# AtariPunkConsole.net
KiCad netlist of a schematic drawn in EAGLE
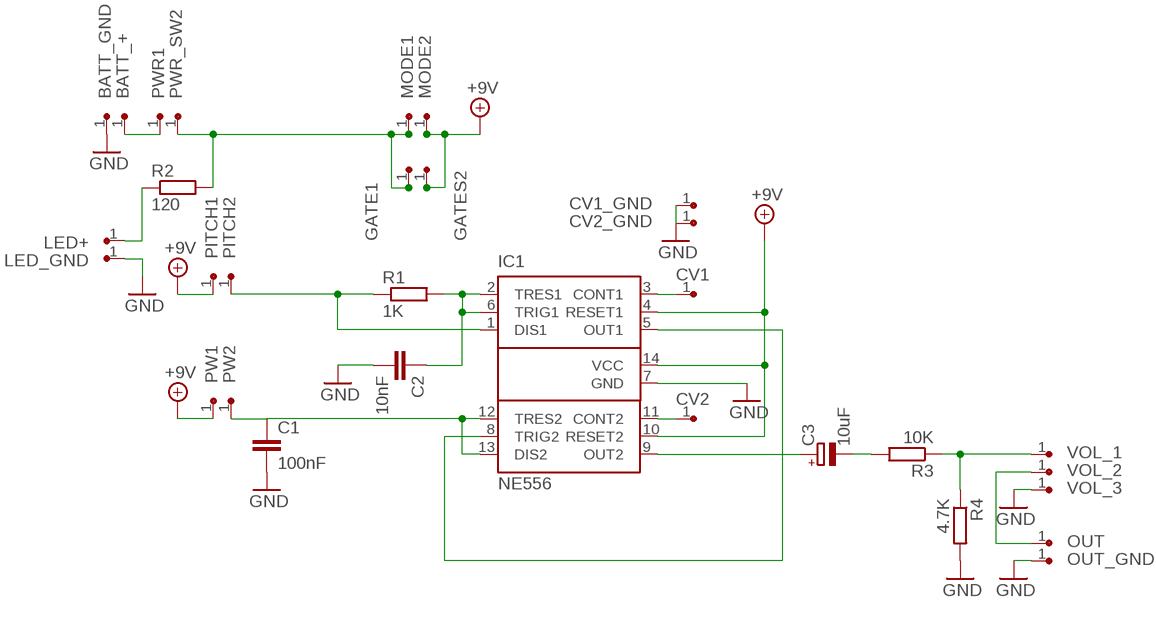
[diagram p0: schematic, sheet 1]

(export (version "E")
  (design (tool "Eeschema 10.0.6"))
  (components
    (comp (ref "BATT_+")
      (value "CV1")
      (footprint "eagle-import:SINGLE_PAD")
      (libsource (lib "eagle-import") (part "SINGLE_PAD"))
    )
    (comp (ref "BATT_GND")
      (value "CV1")
      (footprint "eagle-import:SINGLE_PAD")
      (libsource (lib "eagle-import") (part "SINGLE_PAD"))
    )
    (comp (ref "C1")
      (value "100nF")
      (footprint "eagle-import:C050-025X075")
      (libsource (lib "eagle-import") (part "C-EU050-025X075"))
    )
    (comp (ref "C2")
      (value "10nF")
      (footprint "eagle-import:C050-025X075")
      (libsource (lib "eagle-import") (part "C-EU050-025X075"))
    )
    (comp (ref "C3")
      (value "10uF")
      (footprint "eagle-import:E5-5")
      (libsource (lib "eagle-import") (part "CPOL-EUE5-5"))
    )
    (comp (ref "CV1")
      (value "CV1")
      (footprint "eagle-import:SINGLE_PAD")
      (libsource (lib "eagle-import") (part "SINGLE_PAD"))
    )
    (comp (ref "CV1_GND")
      (value "CV1")
      (footprint "eagle-import:SINGLE_PAD")
      (libsource (lib "eagle-import") (part "SINGLE_PAD"))
    )
    (comp (ref "CV2")
      (value "CV1")
      (footprint "eagle-import:SINGLE_PAD")
      (libsource (lib "eagle-import") (part "SINGLE_PAD"))
    )
    (comp (ref "CV2_GND")
      (value "CV1")
      (footprint "eagle-import:SINGLE_PAD")
      (libsource (lib "eagle-import") (part "SINGLE_PAD"))
    )
    (comp (ref "GATE1")
      (value "CV1")
      (footprint "eagle-import:SINGLE_PAD")
      (libsource (lib "eagle-import") (part "SINGLE_PAD"))
    )
    (comp (ref "GATES2")
      (value "CV1")
      (footprint "eagle-import:SINGLE_PAD")
      (libsource (lib "eagle-import") (part "SINGLE_PAD"))
    )
    (comp (ref "IC1")
      (value "NE556")
      (footprint "eagle-import:DIL14")
      (libsource (lib "eagle-import") (part "NE556"))
    )
    (comp (ref "LED+")
      (value "CV1")
      (footprint "eagle-import:SINGLE_PAD")
      (libsource (lib "eagle-import") (part "SINGLE_PAD"))
    )
    (comp (ref "LED_GND")
      (value "CV1")
      (footprint "eagle-import:SINGLE_PAD")
      (libsource (lib "eagle-import") (part "SINGLE_PAD"))
    )
    (comp (ref "MODE1")
      (value "CV1")
      (footprint "eagle-import:SINGLE_PAD")
      (libsource (lib "eagle-import") (part "SINGLE_PAD"))
    )
    (comp (ref "MODE2")
      (value "CV1")
      (footprint "eagle-import:SINGLE_PAD")
      (libsource (lib "eagle-import") (part "SINGLE_PAD"))
    )
    (comp (ref "OUT")
      (value "CV1")
      (footprint "eagle-import:SINGLE_PAD")
      (libsource (lib "eagle-import") (part "SINGLE_PAD"))
    )
    (comp (ref "OUT_GND")
      (value "CV1")
      (footprint "eagle-import:SINGLE_PAD")
      (libsource (lib "eagle-import") (part "SINGLE_PAD"))
    )
    (comp (ref "PITCH1")
      (value "CV1")
      (footprint "eagle-import:SINGLE_PAD")
      (libsource (lib "eagle-import") (part "SINGLE_PAD"))
    )
    (comp (ref "PITCH2")
      (value "CV1")
      (footprint "eagle-import:SINGLE_PAD")
      (libsource (lib "eagle-import") (part "SINGLE_PAD"))
    )
    (comp (ref "PW1")
      (value "CV1")
      (footprint "eagle-import:SINGLE_PAD")
      (libsource (lib "eagle-import") (part "SINGLE_PAD"))
    )
    (comp (ref "PW2")
      (value "CV1")
      (footprint "eagle-import:SINGLE_PAD")
      (libsource (lib "eagle-import") (part "SINGLE_PAD"))
    )
    (comp (ref "PWR1")
      (value "CV1")
      (footprint "eagle-import:SINGLE_PAD")
      (libsource (lib "eagle-import") (part "SINGLE_PAD"))
    )
    (comp (ref "PWR_SW2")
      (value "CV1")
      (footprint "eagle-import:SINGLE_PAD")
      (libsource (lib "eagle-import") (part "SINGLE_PAD"))
    )
    (comp (ref "R1")
      (value "1K")
      (footprint "eagle-import:0204_7")
      (libsource (lib "eagle-import") (part "R-EU_0204/7"))
    )
    (comp (ref "R2")
      (value "120")
      (footprint "eagle-import:0204_7")
      (libsource (lib "eagle-import") (part "R-EU_0204/7"))
    )
    (comp (ref "R3")
      (value "10K")
      (footprint "eagle-import:0204_7")
      (libsource (lib "eagle-import") (part "R-EU_0204/7"))
    )
    (comp (ref "R4")
      (value "4.7K")
      (footprint "eagle-import:0204_7")
      (libsource (lib "eagle-import") (part "R-EU_0204/7"))
    )
    (comp (ref "VOL_1")
      (value "CV1")
      (footprint "eagle-import:SINGLE_PAD")
      (libsource (lib "eagle-import") (part "SINGLE_PAD"))
    )
    (comp (ref "VOL_2")
      (value "CV1")
      (footprint "eagle-import:SINGLE_PAD")
      (libsource (lib "eagle-import") (part "SINGLE_PAD"))
    )
    (comp (ref "VOL_3")
      (value "CV1")
      (footprint "eagle-import:SINGLE_PAD")
      (libsource (lib "eagle-import") (part "SINGLE_PAD"))
    )
  )
  (nets
    (net (code "1") (name "+9V") (class "Default")
      (node (ref "GATES2") (pin "1") (pinfunction "1_1") (pintype "passive"))
      (node (ref "IC1") (pin "10") (pinfunction "RESET2_10") (pintype "input"))
      (node (ref "IC1") (pin "14") (pinfunction "VCC_14") (pintype "power_in"))
      (node (ref "IC1") (pin "4") (pinfunction "RESET1_4") (pintype "input"))
      (node (ref "MODE2") (pin "1") (pinfunction "1_1") (pintype "passive"))
      (node (ref "PITCH1") (pin "1") (pinfunction "1_1") (pintype "passive"))
      (node (ref "PW1") (pin "1") (pinfunction "1_1") (pintype "passive"))
    )
    (net (code "2") (name "GND") (class "Default")
      (node (ref "BATT_GND") (pin "1") (pinfunction "1_1") (pintype "passive"))
      (node (ref "C1") (pin "2") (pinfunction "2_2") (pintype "passive"))
      (node (ref "C2") (pin "2") (pinfunction "2_2") (pintype "passive"))
      (node (ref "CV1_GND") (pin "1") (pinfunction "1_1") (pintype "passive"))
      (node (ref "CV2_GND") (pin "1") (pinfunction "1_1") (pintype "passive"))
      (node (ref "IC1") (pin "7") (pinfunction "GND_7") (pintype "power_in"))
      (node (ref "LED_GND") (pin "1") (pinfunction "1_1") (pintype "passive"))
      (node (ref "OUT_GND") (pin "1") (pinfunction "1_1") (pintype "passive"))
      (node (ref "R4") (pin "2") (pinfunction "2_2") (pintype "passive"))
      (node (ref "VOL_3") (pin "1") (pinfunction "1_1") (pintype "passive"))
    )
    (net (code "3") (name "Net-(BATT_+-Pad1)") (class "Default")
      (node (ref "BATT_+") (pin "1") (pinfunction "1_1") (pintype "passive"))
      (node (ref "PWR1") (pin "1") (pinfunction "1_1") (pintype "passive"))
    )
    (net (code "4") (name "Net-(C3-Pad-)") (class "Default")
      (node (ref "C3") (pin "-") (pinfunction "-_-") (pintype "passive"))
      (node (ref "R3") (pin "2") (pinfunction "2_2") (pintype "passive"))
    )
    (net (code "5") (name "Net-(GATE1-Pad1)") (class "Default")
      (node (ref "GATE1") (pin "1") (pinfunction "1_1") (pintype "passive"))
      (node (ref "MODE1") (pin "1") (pinfunction "1_1") (pintype "passive"))
      (node (ref "PWR_SW2") (pin "1") (pinfunction "1_1") (pintype "passive"))
      (node (ref "R2") (pin "2") (pinfunction "2_2") (pintype "passive"))
    )
    (net (code "6") (name "Net-(IC1-CONT1)") (class "Default")
      (node (ref "CV1") (pin "1") (pinfunction "1_1") (pintype "passive"))
      (node (ref "IC1") (pin "3") (pinfunction "CONT1_3") (pintype "input"))
    )
    (net (code "7") (name "Net-(IC1-CONT2)") (class "Default")
      (node (ref "CV2") (pin "1") (pinfunction "1_1") (pintype "passive"))
      (node (ref "IC1") (pin "11") (pinfunction "CONT2_11") (pintype "input"))
    )
    (net (code "8") (name "Net-(IC1-DIS1)") (class "Default")
      (node (ref "IC1") (pin "1") (pinfunction "DIS1_1") (pintype "input"))
      (node (ref "PITCH2") (pin "1") (pinfunction "1_1") (pintype "passive"))
      (node (ref "R1") (pin "1") (pinfunction "1_1") (pintype "passive"))
    )
    (net (code "9") (name "Net-(IC1-DIS2)") (class "Default")
      (node (ref "C1") (pin "1") (pinfunction "1_1") (pintype "passive"))
      (node (ref "IC1") (pin "12") (pinfunction "TRES2_12") (pintype "input"))
      (node (ref "IC1") (pin "13") (pinfunction "DIS2_13") (pintype "input"))
      (node (ref "PW2") (pin "1") (pinfunction "1_1") (pintype "passive"))
    )
    (net (code "10") (name "Net-(IC1-OUT1)") (class "Default")
      (node (ref "IC1") (pin "5") (pinfunction "OUT1_5") (pintype "output"))
      (node (ref "IC1") (pin "8") (pinfunction "TRIG2_8") (pintype "input"))
    )
    (net (code "11") (name "Net-(IC1-OUT2)") (class "Default")
      (node (ref "C3") (pin "+") (pinfunction "+_+") (pintype "passive"))
      (node (ref "IC1") (pin "9") (pinfunction "OUT2_9") (pintype "output"))
    )
    (net (code "12") (name "Net-(IC1-TRES1)") (class "Default")
      (node (ref "C2") (pin "1") (pinfunction "1_1") (pintype "passive"))
      (node (ref "IC1") (pin "2") (pinfunction "TRES1_2") (pintype "input"))
      (node (ref "IC1") (pin "6") (pinfunction "TRIG1_6") (pintype "input"))
      (node (ref "R1") (pin "2") (pinfunction "2_2") (pintype "passive"))
    )
    (net (code "13") (name "Net-(LED+-Pad1)") (class "Default")
      (node (ref "LED+") (pin "1") (pinfunction "1_1") (pintype "passive"))
      (node (ref "R2") (pin "1") (pinfunction "1_1") (pintype "passive"))
    )
    (net (code "14") (name "Net-(OUT-Pad1)") (class "Default")
      (node (ref "OUT") (pin "1") (pinfunction "1_1") (pintype "passive"))
      (node (ref "VOL_2") (pin "1") (pinfunction "1_1") (pintype "passive"))
    )
    (net (code "15") (name "Net-(R3-Pad1)") (class "Default")
      (node (ref "R3") (pin "1") (pinfunction "1_1") (pintype "passive"))
      (node (ref "R4") (pin "1") (pinfunction "1_1") (pintype "passive"))
      (node (ref "VOL_1") (pin "1") (pinfunction "1_1") (pintype "passive"))
    )
  )
)
